# Switch.net
KiCad netlist of a schematic drawn in Altium Designer
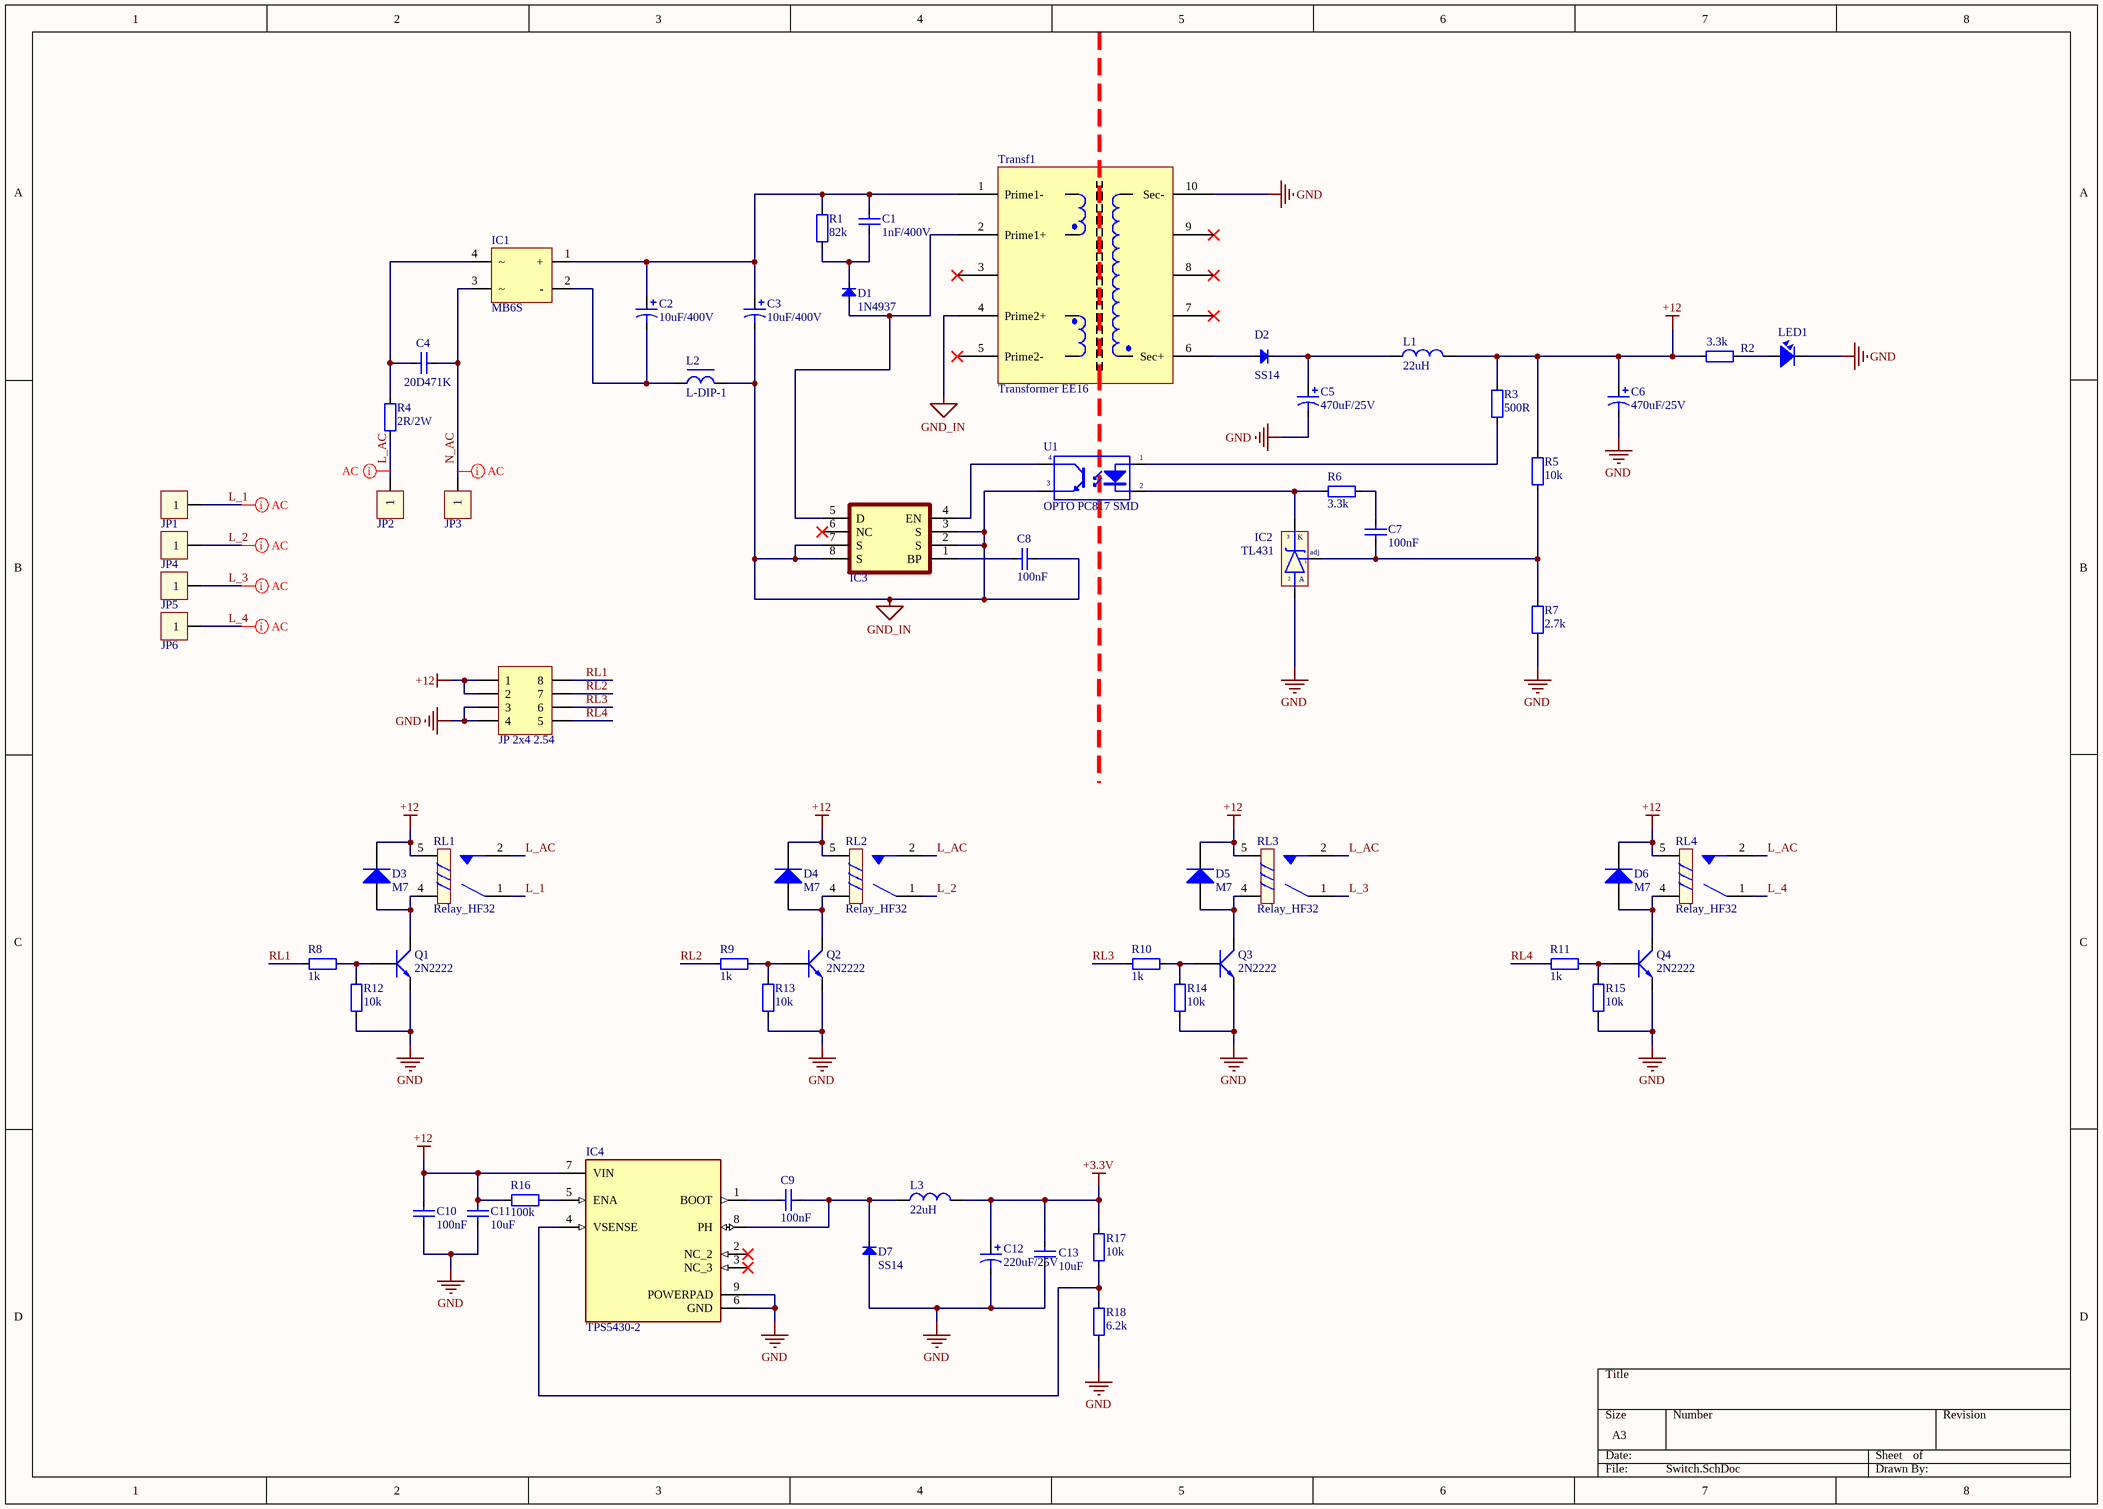
[diagram p0: Switch.SchDoc]

(export (version "E")
  (design (tool "Eeschema 10.0.6"))
  (components
    (comp (ref "C1")
      (value "1nF/400V")
      (footprint "103/2KV")
      (description "CAP CERAMIC")
      (fields (field (name "PUBLISHER") "Altium Limited"))
      (libsource (lib "My Library") (part "Cap2KV"))
    )
    (comp (ref "C2")
      (value "10uF/400V")
      (footprint "C10mm")
      (description "Polarized Capacitor (Axial)")
      (fields (field (name "PUBLISHER") "Altium Limited"))
      (libsource (lib "My Library") (part "Cap Pol"))
    )
    (comp (ref "C3")
      (value "10uF/400V")
      (footprint "C10mm")
      (description "Polarized Capacitor (Axial)")
      (fields (field (name "PUBLISHER") "Altium Limited"))
      (libsource (lib "My Library") (part "Cap Pol"))
    )
    (comp (ref "C4")
      (value "20D471K")
      (footprint "103/2KV")
      (description "Varistor")
      (fields (field (name "PUBLISHER") "Altium Limited"))
      (libsource (lib "My Library") (part "Cap2KV"))
    )
    (comp (ref "C5")
      (value "470uF/25V")
      (footprint "C8mm")
      (description "470uF 25V 8x12mm")
      (fields (field (name "PUBLISHER") "Altium Limited"))
      (libsource (lib "My Library") (part "Cap Pol"))
    )
    (comp (ref "C6")
      (value "470uF/25V")
      (footprint "C8mm")
      (description "470uF 25V 8x12mm")
      (fields (field (name "PUBLISHER") "Altium Limited"))
      (libsource (lib "My Library") (part "Cap Pol"))
    )
    (comp (ref "C7")
      (value "100nF")
      (footprint "CAP_0603")
      (description "Capacitor")
      (fields (field (name "PUBLISHER") "Altium Limited"))
      (libsource (lib "My Library") (part "CapSMD"))
    )
    (comp (ref "C8")
      (value "100nF")
      (footprint "CAP_0603")
      (description "Capacitor")
      (fields (field (name "PUBLISHER") "Altium Limited"))
      (libsource (lib "My Library") (part "CapSMD"))
    )
    (comp (ref "C9")
      (value "100nF")
      (footprint "CAP_0603")
      (description "Capacitor")
      (fields (field (name "PUBLISHER") "Altium Limited"))
      (libsource (lib "My Library") (part "CapSMD"))
    )
    (comp (ref "C10")
      (value "100nF")
      (footprint "CAP_0603")
      (description "Capacitor")
      (fields (field (name "PUBLISHER") "Altium Limited"))
      (libsource (lib "My Library") (part "CapSMD"))
    )
    (comp (ref "C11")
      (value "10uF")
      (footprint "CAP_0603")
      (description "Capacitor")
      (fields (field (name "PUBLISHER") "Altium Limited"))
      (libsource (lib "My Library") (part "CapSMD"))
    )
    (comp (ref "C12")
      (value "220uF/25V")
      (footprint "C8mm")
      (description "470uF 25V 8x12mm")
      (fields (field (name "PUBLISHER") "Altium Limited"))
      (libsource (lib "My Library") (part "Cap Pol"))
    )
    (comp (ref "C13")
      (value "10uF")
      (footprint "CAP_0603")
      (description "Capacitor")
      (fields (field (name "PUBLISHER") "Altium Limited"))
      (libsource (lib "My Library") (part "CapSMD"))
    )
    (comp (ref "D1")
      (value "1N4937")
      (footprint "DIO-1AN")
      (description "Diode Schottky\r\n1N4937")
      (fields (field (name "PUBLISHER") "Altium Limited"))
      (libsource (lib "My Library") (part "Diode SMD"))
    )
    (comp (ref "D2")
      (value "SS14")
      (footprint "DO-214AC(SMA)")
      (description "SS34 Diode Schottky 3A 40V SMA(DO-214AC)")
      (fields (field (name "PUBLISHER") "Altium Limited"))
      (libsource (lib "My Library") (part "Diode SMD"))
    )
    (comp (ref "D3")
      (value "M7")
      (footprint "DIODE SMA")
      (description "Dán")
      (libsource (lib "Altium_Lib_by_KhueNguyenCreator") (part "Diode M7 ( 4007 )"))
    )
    (comp (ref "D4")
      (value "M7")
      (footprint "DIODE SMA")
      (description "Dán")
      (libsource (lib "Altium_Lib_by_KhueNguyenCreator") (part "Diode M7 ( 4007 )"))
    )
    (comp (ref "D5")
      (value "M7")
      (footprint "DIODE SMA")
      (description "Dán")
      (libsource (lib "Altium_Lib_by_KhueNguyenCreator") (part "Diode M7 ( 4007 )"))
    )
    (comp (ref "D6")
      (value "M7")
      (footprint "DIODE SMA")
      (description "Dán")
      (libsource (lib "Altium_Lib_by_KhueNguyenCreator") (part "Diode M7 ( 4007 )"))
    )
    (comp (ref "D7")
      (value "SS14")
      (footprint "DO-214AC(SMA)")
      (description "SS34 Diode Schottky 3A 40V SMA(DO-214AC)")
      (fields (field (name "PUBLISHER") "Altium Limited"))
      (libsource (lib "My Library") (part "Diode SMD"))
    )
    (comp (ref "IC1") (value "MB6S") (footprint "MB6S") (libsource (lib "My Library") (part "MB6S")))
    (comp (ref "IC2")
      (value "TL431")
      (footprint "TL431_SOT")
      (description "Programmable Shunt Regulator")
      (libsource (lib "My Library") (part "TL431"))
    )
    (comp (ref "IC3")
      (value "TNY264")
      (footprint "DIP8")
      (description "Enhanced, Energy Efficient, Low Power Off-line Switcher")
      (libsource (lib "My Library") (part "TNY264"))
    )
    (comp (ref "IC4")
      (value "TPS5430-2")
      (footprint "TPS5430")
      (libsource (lib "My Library") (part "TPS5430-2"))
    )
    (comp (ref "JP1") (value "Coc_dong") (footprint "Coc_dong") (libsource (lib "") (part "Coc_dong_1")))
    (comp (ref "JP2")
      (value "Coc_dong")
      (footprint "Coc_dong")
      (libsource (lib "My Library") (part "Coc_dong"))
    )
    (comp (ref "JP3")
      (value "Coc_dong")
      (footprint "Coc_dong")
      (libsource (lib "My Library") (part "Coc_dong"))
    )
    (comp (ref "JP4") (value "Coc_dong") (footprint "Coc_dong") (libsource (lib "") (part "Coc_dong_1")))
    (comp (ref "JP5") (value "Coc_dong") (footprint "Coc_dong") (libsource (lib "") (part "Coc_dong_1")))
    (comp (ref "JP6") (value "Coc_dong") (footprint "Coc_dong") (libsource (lib "") (part "Coc_dong_1")))
    (comp (ref "JP7")
      (value "JP 2x4 2.54")
      (footprint "JP 2x4 DT")
      (description "Cắm")
      (libsource (lib "Altium_Lib_by_KhueNguyenCreator") (part "JP 2x4 2.54 Duc Thang"))
    )
    (comp (ref "L1")
      (value "22uH")
      (footprint "Inductor")
      (description "CD73R 22uH 1.23A 7345")
      (libsource (lib "My Library") (part "Inductor"))
    )
    (comp (ref "L2")
      (value "L-DIP-1")
      (footprint "Inductor")
      (description "Inductor")
      (libsource (lib "My Library") (part "L-DIP-1"))
    )
    (comp (ref "L3")
      (value "22uH")
      (footprint "L_SMD")
      (description "CD73R 22uH 1.23A 7345")
      (libsource (lib "My Library") (part "Inductor"))
    )
    (comp (ref "LED1")
      (value "LED")
      (footprint "LED-0805-Red")
      (description "LED Single colour Green and Red")
      (libsource (lib "My Library") (part "LED"))
    )
    (comp (ref "Q1")
      (value "2N2222")
      (footprint "SOT23")
      (description "NPN transistor")
      (libsource (lib "Altium_Lib_by_KhueNguyenCreator") (part "C1815 HF SMD"))
    )
    (comp (ref "Q2")
      (value "2N2222")
      (footprint "SOT23")
      (description "NPN transistor")
      (libsource (lib "Altium_Lib_by_KhueNguyenCreator") (part "C1815 HF SMD"))
    )
    (comp (ref "Q3")
      (value "2N2222")
      (footprint "SOT23")
      (description "NPN transistor")
      (libsource (lib "Altium_Lib_by_KhueNguyenCreator") (part "C1815 HF SMD"))
    )
    (comp (ref "Q4")
      (value "2N2222")
      (footprint "SOT23")
      (description "NPN transistor")
      (libsource (lib "Altium_Lib_by_KhueNguyenCreator") (part "C1815 HF SMD"))
    )
    (comp (ref "R1")
      (value "82k")
      (footprint "RES-SMD-2512")
      (description "Resistor")
      (fields
        (field (name "MANUFACTURER") "Generic Components")
        (field (name "PUBLISHER") "Altium Hobart Technology Centre")
      )
      (libsource (lib "My Library") (part "Resistor - SMD"))
    )
    (comp (ref "R2")
      (value "3.3k")
      (footprint "RES-SMD-0603")
      (description "Resistor")
      (fields
        (field (name "MANUFACTURER") "Generic Components")
        (field (name "PUBLISHER") "Altium Hobart Technology Centre")
      )
      (libsource (lib "My Library") (part "Resistor - SMD"))
    )
    (comp (ref "R3")
      (value "500R")
      (footprint "RES-SMD-0603")
      (description "Resistor")
      (fields
        (field (name "MANUFACTURER") "Generic Components")
        (field (name "PUBLISHER") "Altium Hobart Technology Centre")
      )
      (libsource (lib "My Library") (part "Resistor - SMD"))
    )
    (comp (ref "R4")
      (value "2R/2W")
      (footprint "RES-1WW")
      (description "Resistor")
      (fields
        (field (name "MANUFACTURER") "Generic Components")
        (field (name "PUBLISHER") "Altium Hobart Technology Centre")
      )
      (libsource (lib "My Library") (part "Resistor - SMD"))
    )
    (comp (ref "R5")
      (value "10k")
      (footprint "RES-SMD-0603")
      (description "Resistor")
      (fields
        (field (name "MANUFACTURER") "Generic Components")
        (field (name "PUBLISHER") "Altium Hobart Technology Centre")
      )
      (libsource (lib "My Library") (part "Resistor - SMD"))
    )
    (comp (ref "R6")
      (value "3.3k")
      (footprint "RES-SMD-0603")
      (description "Resistor")
      (fields
        (field (name "MANUFACTURER") "Generic Components")
        (field (name "PUBLISHER") "Altium Hobart Technology Centre")
      )
      (libsource (lib "My Library") (part "Resistor - SMD"))
    )
    (comp (ref "R7")
      (value "2.7k")
      (footprint "RES-SMD-0603")
      (description "Resistor")
      (fields
        (field (name "MANUFACTURER") "Generic Components")
        (field (name "PUBLISHER") "Altium Hobart Technology Centre")
      )
      (libsource (lib "My Library") (part "Resistor - SMD"))
    )
    (comp (ref "R8")
      (value "1k")
      (footprint "RES-SMD-0603")
      (description "Resistor")
      (fields
        (field (name "MANUFACTURER") "Generic Components")
        (field (name "PUBLISHER") "Altium Hobart Technology Centre")
      )
      (libsource (lib "My Library") (part "Resistor - SMD"))
    )
    (comp (ref "R9")
      (value "1k")
      (footprint "RES-SMD-0603")
      (description "Resistor")
      (fields
        (field (name "MANUFACTURER") "Generic Components")
        (field (name "PUBLISHER") "Altium Hobart Technology Centre")
      )
      (libsource (lib "My Library") (part "Resistor - SMD"))
    )
    (comp (ref "R10")
      (value "1k")
      (footprint "RES-SMD-0603")
      (description "Resistor")
      (fields
        (field (name "MANUFACTURER") "Generic Components")
        (field (name "PUBLISHER") "Altium Hobart Technology Centre")
      )
      (libsource (lib "My Library") (part "Resistor - SMD"))
    )
    (comp (ref "R11")
      (value "1k")
      (footprint "RES-SMD-0603")
      (description "Resistor")
      (fields
        (field (name "MANUFACTURER") "Generic Components")
        (field (name "PUBLISHER") "Altium Hobart Technology Centre")
      )
      (libsource (lib "My Library") (part "Resistor - SMD"))
    )
    (comp (ref "R12")
      (value "10k")
      (footprint "RES-SMD-0603")
      (description "Resistor")
      (fields
        (field (name "MANUFACTURER") "Generic Components")
        (field (name "PUBLISHER") "Altium Hobart Technology Centre")
      )
      (libsource (lib "My Library") (part "Resistor - SMD"))
    )
    (comp (ref "R13")
      (value "10k")
      (footprint "RES-SMD-0603")
      (description "Resistor")
      (fields
        (field (name "MANUFACTURER") "Generic Components")
        (field (name "PUBLISHER") "Altium Hobart Technology Centre")
      )
      (libsource (lib "My Library") (part "Resistor - SMD"))
    )
    (comp (ref "R14")
      (value "10k")
      (footprint "RES-SMD-0603")
      (description "Resistor")
      (fields
        (field (name "MANUFACTURER") "Generic Components")
        (field (name "PUBLISHER") "Altium Hobart Technology Centre")
      )
      (libsource (lib "My Library") (part "Resistor - SMD"))
    )
    (comp (ref "R15")
      (value "10k")
      (footprint "RES-SMD-0603")
      (description "Resistor")
      (fields
        (field (name "MANUFACTURER") "Generic Components")
        (field (name "PUBLISHER") "Altium Hobart Technology Centre")
      )
      (libsource (lib "My Library") (part "Resistor - SMD"))
    )
    (comp (ref "R16")
      (value "100k")
      (footprint "RES-SMD-0603")
      (description "Resistor")
      (fields
        (field (name "MANUFACTURER") "Generic Components")
        (field (name "PUBLISHER") "Altium Hobart Technology Centre")
      )
      (libsource (lib "My Library") (part "Resistor - SMD"))
    )
    (comp (ref "R17")
      (value "10k")
      (footprint "RES-SMD-0603")
      (description "Resistor")
      (fields
        (field (name "MANUFACTURER") "Generic Components")
        (field (name "PUBLISHER") "Altium Hobart Technology Centre")
      )
      (libsource (lib "My Library") (part "Resistor - SMD"))
    )
    (comp (ref "R18")
      (value "6.2k")
      (footprint "RES-SMD-0603")
      (description "Resistor")
      (fields
        (field (name "MANUFACTURER") "Generic Components")
        (field (name "PUBLISHER") "Altium Hobart Technology Centre")
      )
      (libsource (lib "My Library") (part "Resistor - SMD"))
    )
    (comp (ref "RL1")
      (value "Relay_HF32")
      (footprint "HF32F")
      (libsource (lib "My Library") (part "Relay_HF32"))
    )
    (comp (ref "RL2")
      (value "Relay_HF32")
      (footprint "HF32F")
      (libsource (lib "My Library") (part "Relay_HF32"))
    )
    (comp (ref "RL3")
      (value "Relay_HF32")
      (footprint "HF32F")
      (libsource (lib "My Library") (part "Relay_HF32"))
    )
    (comp (ref "RL4")
      (value "Relay_HF32")
      (footprint "HF32F")
      (libsource (lib "My Library") (part "Relay_HF32"))
    )
    (comp (ref "Transf1")
      (value "Transformer EE16")
      (footprint "Transformer SW")
      (libsource (lib "My Library") (part "Tranformer EE16"))
    )
    (comp (ref "U1")
      (value "OPTO PC817 SMD")
      (footprint "SOP4")
      (description "Single Opto")
      (libsource (lib "Altium_Lib_by_KhueNguyenCreator") (part "OPTO PC817 SMD"))
    )
  )
  (nets
    (net (code "1") (name "+3.3V") (class "Default")
      (node (ref "C12") (pin "1") (pinfunction "1_1") (pintype "passive"))
      (node (ref "C13") (pin "1") (pinfunction "1_1") (pintype "passive"))
      (node (ref "L3") (pin "2") (pinfunction "2_2") (pintype "passive"))
      (node (ref "R17") (pin "2") (pinfunction "2_2") (pintype "passive"))
    )
    (net (code "2") (name "+12") (class "Default")
      (node (ref "C10") (pin "2") (pinfunction "2_2") (pintype "passive"))
      (node (ref "C11") (pin "2") (pinfunction "2_2") (pintype "passive"))
      (node (ref "C6") (pin "1") (pinfunction "1_1") (pintype "passive"))
      (node (ref "D3") (pin "2") (pinfunction "K_2") (pintype "passive"))
      (node (ref "D4") (pin "2") (pinfunction "K_2") (pintype "passive"))
      (node (ref "D5") (pin "2") (pinfunction "K_2") (pintype "passive"))
      (node (ref "D6") (pin "2") (pinfunction "K_2") (pintype "passive"))
      (node (ref "IC4") (pin "7") (pinfunction "VIN_7") (pintype "power_in"))
      (node (ref "JP7") (pin "1") (pinfunction "1_1") (pintype "passive"))
      (node (ref "JP7") (pin "2") (pinfunction "2_2") (pintype "passive"))
      (node (ref "L1") (pin "2") (pinfunction "2_2") (pintype "passive"))
      (node (ref "R16") (pin "1") (pinfunction "1_1") (pintype "passive"))
      (node (ref "R2") (pin "2") (pinfunction "2_2") (pintype "passive"))
      (node (ref "R3") (pin "1") (pinfunction "1_1") (pintype "passive"))
      (node (ref "R5") (pin "1") (pinfunction "1_1") (pintype "passive"))
      (node (ref "RL1") (pin "5") (pinfunction "5_5") (pintype "passive"))
      (node (ref "RL2") (pin "5") (pinfunction "5_5") (pintype "passive"))
      (node (ref "RL3") (pin "5") (pinfunction "5_5") (pintype "passive"))
      (node (ref "RL4") (pin "5") (pinfunction "5_5") (pintype "passive"))
    )
    (net (code "3") (name "/L_1") (class "Default")
      (node (ref "JP1") (pin "1") (pinfunction "1_1") (pintype "passive"))
      (node (ref "RL1") (pin "1") (pinfunction "1_1") (pintype "passive"))
    )
    (net (code "4") (name "/L_2") (class "Default")
      (node (ref "JP4") (pin "1") (pinfunction "1_1") (pintype "passive"))
      (node (ref "RL2") (pin "1") (pinfunction "1_1") (pintype "passive"))
    )
    (net (code "5") (name "/L_3") (class "Default")
      (node (ref "JP5") (pin "1") (pinfunction "1_1") (pintype "passive"))
      (node (ref "RL3") (pin "1") (pinfunction "1_1") (pintype "passive"))
    )
    (net (code "6") (name "/L_4") (class "Default")
      (node (ref "JP6") (pin "1") (pinfunction "1_1") (pintype "passive"))
      (node (ref "RL4") (pin "1") (pinfunction "1_1") (pintype "passive"))
    )
    (net (code "7") (name "/L_AC") (class "Default")
      (node (ref "JP2") (pin "1") (pinfunction "1_1") (pintype "passive"))
      (node (ref "R4") (pin "2") (pinfunction "2_2") (pintype "passive"))
      (node (ref "RL1") (pin "2") (pinfunction "2_2") (pintype "passive"))
      (node (ref "RL2") (pin "2") (pinfunction "2_2") (pintype "passive"))
      (node (ref "RL3") (pin "2") (pinfunction "2_2") (pintype "passive"))
      (node (ref "RL4") (pin "2") (pinfunction "2_2") (pintype "passive"))
    )
    (net (code "8") (name "/N_AC") (class "Default")
      (node (ref "C4") (pin "1") (pinfunction "1_1") (pintype "passive"))
      (node (ref "IC1") (pin "3") (pinfunction "~_3") (pintype "passive"))
      (node (ref "JP3") (pin "1") (pinfunction "1_1") (pintype "passive"))
    )
    (net (code "9") (name "/RL1") (class "Default")
      (node (ref "JP7") (pin "8") (pinfunction "8_8") (pintype "passive"))
      (node (ref "R8") (pin "1") (pinfunction "1_1") (pintype "passive"))
    )
    (net (code "10") (name "/RL2") (class "Default")
      (node (ref "JP7") (pin "7") (pinfunction "7_7") (pintype "passive"))
      (node (ref "R9") (pin "1") (pinfunction "1_1") (pintype "passive"))
    )
    (net (code "11") (name "/RL3") (class "Default")
      (node (ref "JP7") (pin "6") (pinfunction "6_6") (pintype "passive"))
      (node (ref "R10") (pin "1") (pinfunction "1_1") (pintype "passive"))
    )
    (net (code "12") (name "/RL4") (class "Default")
      (node (ref "JP7") (pin "5") (pinfunction "5_5") (pintype "passive"))
      (node (ref "R11") (pin "1") (pinfunction "1_1") (pintype "passive"))
    )
    (net (code "13") (name "GND") (class "Default")
      (node (ref "C10") (pin "1") (pinfunction "1_1") (pintype "passive"))
      (node (ref "C11") (pin "1") (pinfunction "1_1") (pintype "passive"))
      (node (ref "C12") (pin "2") (pinfunction "2_2") (pintype "passive"))
      (node (ref "C13") (pin "2") (pinfunction "2_2") (pintype "passive"))
      (node (ref "C5") (pin "2") (pinfunction "2_2") (pintype "passive"))
      (node (ref "C6") (pin "2") (pinfunction "2_2") (pintype "passive"))
      (node (ref "D7") (pin "1") (pinfunction "A_1") (pintype "passive"))
      (node (ref "IC2") (pin "2") (pinfunction "A_2") (pintype "passive"))
      (node (ref "IC4") (pin "6") (pinfunction "GND_6") (pintype "power_in"))
      (node (ref "IC4") (pin "9") (pinfunction "POWERPAD_9") (pintype "power_in"))
      (node (ref "JP7") (pin "3") (pinfunction "3_3") (pintype "passive"))
      (node (ref "JP7") (pin "4") (pinfunction "4_4") (pintype "passive"))
      (node (ref "LED1") (pin "2") (pinfunction "2_2") (pintype "passive"))
      (node (ref "Q1") (pin "2") (pinfunction "E_2") (pintype "passive"))
      (node (ref "Q2") (pin "2") (pinfunction "E_2") (pintype "passive"))
      (node (ref "Q3") (pin "2") (pinfunction "E_2") (pintype "passive"))
      (node (ref "Q4") (pin "2") (pinfunction "E_2") (pintype "passive"))
      (node (ref "R12") (pin "1") (pinfunction "1_1") (pintype "passive"))
      (node (ref "R13") (pin "1") (pinfunction "1_1") (pintype "passive"))
      (node (ref "R14") (pin "1") (pinfunction "1_1") (pintype "passive"))
      (node (ref "R15") (pin "1") (pinfunction "1_1") (pintype "passive"))
      (node (ref "R18") (pin "1") (pinfunction "1_1") (pintype "passive"))
      (node (ref "R7") (pin "2") (pinfunction "2_2") (pintype "passive"))
      (node (ref "Transf1") (pin "10") (pinfunction "Sec-_10") (pintype "passive"))
    )
    (net (code "14") (name "GND_IN") (class "Default")
      (node (ref "C3") (pin "2") (pinfunction "2_2") (pintype "passive"))
      (node (ref "C8") (pin "1") (pinfunction "1_1") (pintype "passive"))
      (node (ref "IC3") (pin "2") (pinfunction "S_2") (pintype "power_in"))
      (node (ref "IC3") (pin "3") (pinfunction "S_3") (pintype "power_in"))
      (node (ref "IC3") (pin "7") (pinfunction "S_7") (pintype "power_in"))
      (node (ref "IC3") (pin "8") (pinfunction "S_8") (pintype "power_in"))
      (node (ref "L2") (pin "2") (pinfunction "2_2") (pintype "passive"))
      (node (ref "Transf1") (pin "4") (pinfunction "Prime2+_4") (pintype "passive"))
      (node (ref "U1") (pin "3") (pinfunction "E_3") (pintype "passive"))
    )
    (net (code "15") (name "Net-(C4-Pad2)") (class "Default")
      (node (ref "C4") (pin "2") (pinfunction "2_2") (pintype "passive"))
      (node (ref "IC1") (pin "4") (pinfunction "~_4") (pintype "passive"))
      (node (ref "R4") (pin "1") (pinfunction "1_1") (pintype "passive"))
    )
    (net (code "16") (name "Net-(C7-Pad2)") (class "Default")
      (node (ref "C7") (pin "2") (pinfunction "2_2") (pintype "passive"))
      (node (ref "R6") (pin "2") (pinfunction "2_2") (pintype "passive"))
    )
    (net (code "17") (name "Net-(D1-A)") (class "Default")
      (node (ref "D1") (pin "1") (pinfunction "A_1") (pintype "passive"))
      (node (ref "IC3") (pin "5") (pinfunction "D_5") (pintype "power_in"))
      (node (ref "Transf1") (pin "2") (pinfunction "Prime1+_2") (pintype "passive"))
    )
    (net (code "18") (name "Net-(D1-K)") (class "Default")
      (node (ref "C1") (pin "2") (pinfunction "2_2") (pintype "passive"))
      (node (ref "D1") (pin "2") (pinfunction "K_2") (pintype "passive"))
      (node (ref "R1") (pin "2") (pinfunction "2_2") (pintype "passive"))
    )
    (net (code "19") (name "Net-(D2-A)") (class "Default")
      (node (ref "D2") (pin "1") (pinfunction "A_1") (pintype "passive"))
      (node (ref "Transf1") (pin "6") (pinfunction "Sec+_6") (pintype "passive"))
    )
    (net (code "20") (name "Net-(D2-K)") (class "Default")
      (node (ref "C5") (pin "1") (pinfunction "1_1") (pintype "passive"))
      (node (ref "D2") (pin "2") (pinfunction "K_2") (pintype "passive"))
      (node (ref "L1") (pin "1") (pinfunction "1_1") (pintype "passive"))
    )
    (net (code "21") (name "Net-(D3-A)") (class "Default")
      (node (ref "D3") (pin "1") (pinfunction "A_1") (pintype "passive"))
      (node (ref "Q1") (pin "3") (pinfunction "C_3") (pintype "passive"))
      (node (ref "RL1") (pin "4") (pinfunction "4_4") (pintype "passive"))
    )
    (net (code "22") (name "Net-(D4-A)") (class "Default")
      (node (ref "D4") (pin "1") (pinfunction "A_1") (pintype "passive"))
      (node (ref "Q2") (pin "3") (pinfunction "C_3") (pintype "passive"))
      (node (ref "RL2") (pin "4") (pinfunction "4_4") (pintype "passive"))
    )
    (net (code "23") (name "Net-(D5-A)") (class "Default")
      (node (ref "D5") (pin "1") (pinfunction "A_1") (pintype "passive"))
      (node (ref "Q3") (pin "3") (pinfunction "C_3") (pintype "passive"))
      (node (ref "RL3") (pin "4") (pinfunction "4_4") (pintype "passive"))
    )
    (net (code "24") (name "Net-(D6-A)") (class "Default")
      (node (ref "D6") (pin "1") (pinfunction "A_1") (pintype "passive"))
      (node (ref "Q4") (pin "3") (pinfunction "C_3") (pintype "passive"))
      (node (ref "RL4") (pin "4") (pinfunction "4_4") (pintype "passive"))
    )
    (net (code "25") (name "Net-(D7-K)") (class "Default")
      (node (ref "C9") (pin "1") (pinfunction "1_1") (pintype "passive"))
      (node (ref "D7") (pin "2") (pinfunction "K_2") (pintype "passive"))
      (node (ref "IC4") (pin "8") (pinfunction "PH_8") (pintype "bidirectional"))
      (node (ref "L3") (pin "1") (pinfunction "1_1") (pintype "passive"))
    )
    (net (code "26") (name "Net-(IC1-+)") (class "Default")
      (node (ref "C1") (pin "1") (pinfunction "1_1") (pintype "passive"))
      (node (ref "C2") (pin "1") (pinfunction "1_1") (pintype "passive"))
      (node (ref "C3") (pin "1") (pinfunction "1_1") (pintype "passive"))
      (node (ref "IC1") (pin "1") (pinfunction "+_1") (pintype "passive"))
      (node (ref "R1") (pin "1") (pinfunction "1_1") (pintype "passive"))
      (node (ref "Transf1") (pin "1") (pinfunction "Prime1-_1") (pintype "passive"))
    )
    (net (code "27") (name "Net-(IC1--)") (class "Default")
      (node (ref "C2") (pin "2") (pinfunction "2_2") (pintype "passive"))
      (node (ref "IC1") (pin "2") (pinfunction "-_2") (pintype "passive"))
      (node (ref "L2") (pin "1") (pinfunction "1_1") (pintype "passive"))
    )
    (net (code "28") (name "Net-(IC2-K)") (class "Default")
      (node (ref "IC2") (pin "3") (pinfunction "K_3") (pintype "passive"))
      (node (ref "R6") (pin "1") (pinfunction "1_1") (pintype "passive"))
      (node (ref "U1") (pin "2") (pinfunction "K_2") (pintype "passive"))
    )
    (net (code "29") (name "Net-(IC2-adj)") (class "Default")
      (node (ref "C7") (pin "1") (pinfunction "1_1") (pintype "passive"))
      (node (ref "IC2") (pin "1") (pinfunction "adj_1") (pintype "passive"))
      (node (ref "R5") (pin "2") (pinfunction "2_2") (pintype "passive"))
      (node (ref "R7") (pin "1") (pinfunction "1_1") (pintype "passive"))
    )
    (net (code "30") (name "Net-(IC3-BP)") (class "Default")
      (node (ref "C8") (pin "2") (pinfunction "2_2") (pintype "passive"))
      (node (ref "IC3") (pin "1") (pinfunction "BP_1") (pintype "power_in"))
    )
    (net (code "31") (name "Net-(IC3-EN)") (class "Default")
      (node (ref "IC3") (pin "4") (pinfunction "EN_4") (pintype "power_in"))
      (node (ref "U1") (pin "4") (pinfunction "C_4") (pintype "passive"))
    )
    (net (code "32") (name "Net-(IC4-BOOT)") (class "Default")
      (node (ref "C9") (pin "2") (pinfunction "2_2") (pintype "passive"))
      (node (ref "IC4") (pin "1") (pinfunction "BOOT_1") (pintype "output"))
    )
    (net (code "33") (name "Net-(IC4-ENA)") (class "Default")
      (node (ref "IC4") (pin "5") (pinfunction "ENA_5") (pintype "input"))
      (node (ref "R16") (pin "2") (pinfunction "2_2") (pintype "passive"))
    )
    (net (code "34") (name "Net-(IC4-VSENSE)") (class "Default")
      (node (ref "IC4") (pin "4") (pinfunction "VSENSE_4") (pintype "input"))
      (node (ref "R17") (pin "1") (pinfunction "1_1") (pintype "passive"))
      (node (ref "R18") (pin "2") (pinfunction "2_2") (pintype "passive"))
    )
    (net (code "35") (name "Net-(LED1-Pad1)") (class "Default")
      (node (ref "LED1") (pin "1") (pinfunction "1_1") (pintype "passive"))
      (node (ref "R2") (pin "1") (pinfunction "1_1") (pintype "passive"))
    )
    (net (code "36") (name "Net-(Q1-B)") (class "Default")
      (node (ref "Q1") (pin "1") (pinfunction "B_1") (pintype "passive"))
      (node (ref "R12") (pin "2") (pinfunction "2_2") (pintype "passive"))
      (node (ref "R8") (pin "2") (pinfunction "2_2") (pintype "passive"))
    )
    (net (code "37") (name "Net-(Q2-B)") (class "Default")
      (node (ref "Q2") (pin "1") (pinfunction "B_1") (pintype "passive"))
      (node (ref "R13") (pin "2") (pinfunction "2_2") (pintype "passive"))
      (node (ref "R9") (pin "2") (pinfunction "2_2") (pintype "passive"))
    )
    (net (code "38") (name "Net-(Q3-B)") (class "Default")
      (node (ref "Q3") (pin "1") (pinfunction "B_1") (pintype "passive"))
      (node (ref "R10") (pin "2") (pinfunction "2_2") (pintype "passive"))
      (node (ref "R14") (pin "2") (pinfunction "2_2") (pintype "passive"))
    )
    (net (code "39") (name "Net-(Q4-B)") (class "Default")
      (node (ref "Q4") (pin "1") (pinfunction "B_1") (pintype "passive"))
      (node (ref "R11") (pin "2") (pinfunction "2_2") (pintype "passive"))
      (node (ref "R15") (pin "2") (pinfunction "2_2") (pintype "passive"))
    )
    (net (code "40") (name "Net-(U1-A)") (class "Default")
      (node (ref "R3") (pin "2") (pinfunction "2_2") (pintype "passive"))
      (node (ref "U1") (pin "1") (pinfunction "A_1") (pintype "passive"))
    )
    (net (code "41") (name "unconnected-(IC3-NC-Pad6)") (class "Default")
      (node (ref "IC3") (pin "6") (pinfunction "NC_6") (pintype "power_in+no_connect"))
    )
    (net (code "42") (name "unconnected-(IC4-NC_2-Pad2)") (class "Default")
      (node (ref "IC4") (pin "2") (pinfunction "NC_2_2") (pintype "input+no_connect"))
    )
    (net (code "43") (name "unconnected-(IC4-NC_3-Pad3)") (class "Default")
      (node (ref "IC4") (pin "3") (pinfunction "NC_3_3") (pintype "input+no_connect"))
    )
    (net (code "44") (name "unconnected-(Transf1-Pad3)") (class "Default")
      (node (ref "Transf1") (pin "3") (pintype "passive+no_connect"))
    )
    (net (code "45") (name "unconnected-(Transf1-Pad7)") (class "Default")
      (node (ref "Transf1") (pin "7") (pintype "passive+no_connect"))
    )
    (net (code "46") (name "unconnected-(Transf1-Pad8)") (class "Default")
      (node (ref "Transf1") (pin "8") (pintype "passive+no_connect"))
    )
    (net (code "47") (name "unconnected-(Transf1-Pad9)") (class "Default")
      (node (ref "Transf1") (pin "9") (pintype "passive+no_connect"))
    )
    (net (code "48") (name "unconnected-(Transf1-Prime2--Pad5)") (class "Default")
      (node (ref "Transf1") (pin "5") (pinfunction "Prime2-_5") (pintype "passive+no_connect"))
    )
  )
)
